# Schematic_IR__1_1.net
KiCad netlist of a schematic drawn in EAGLE
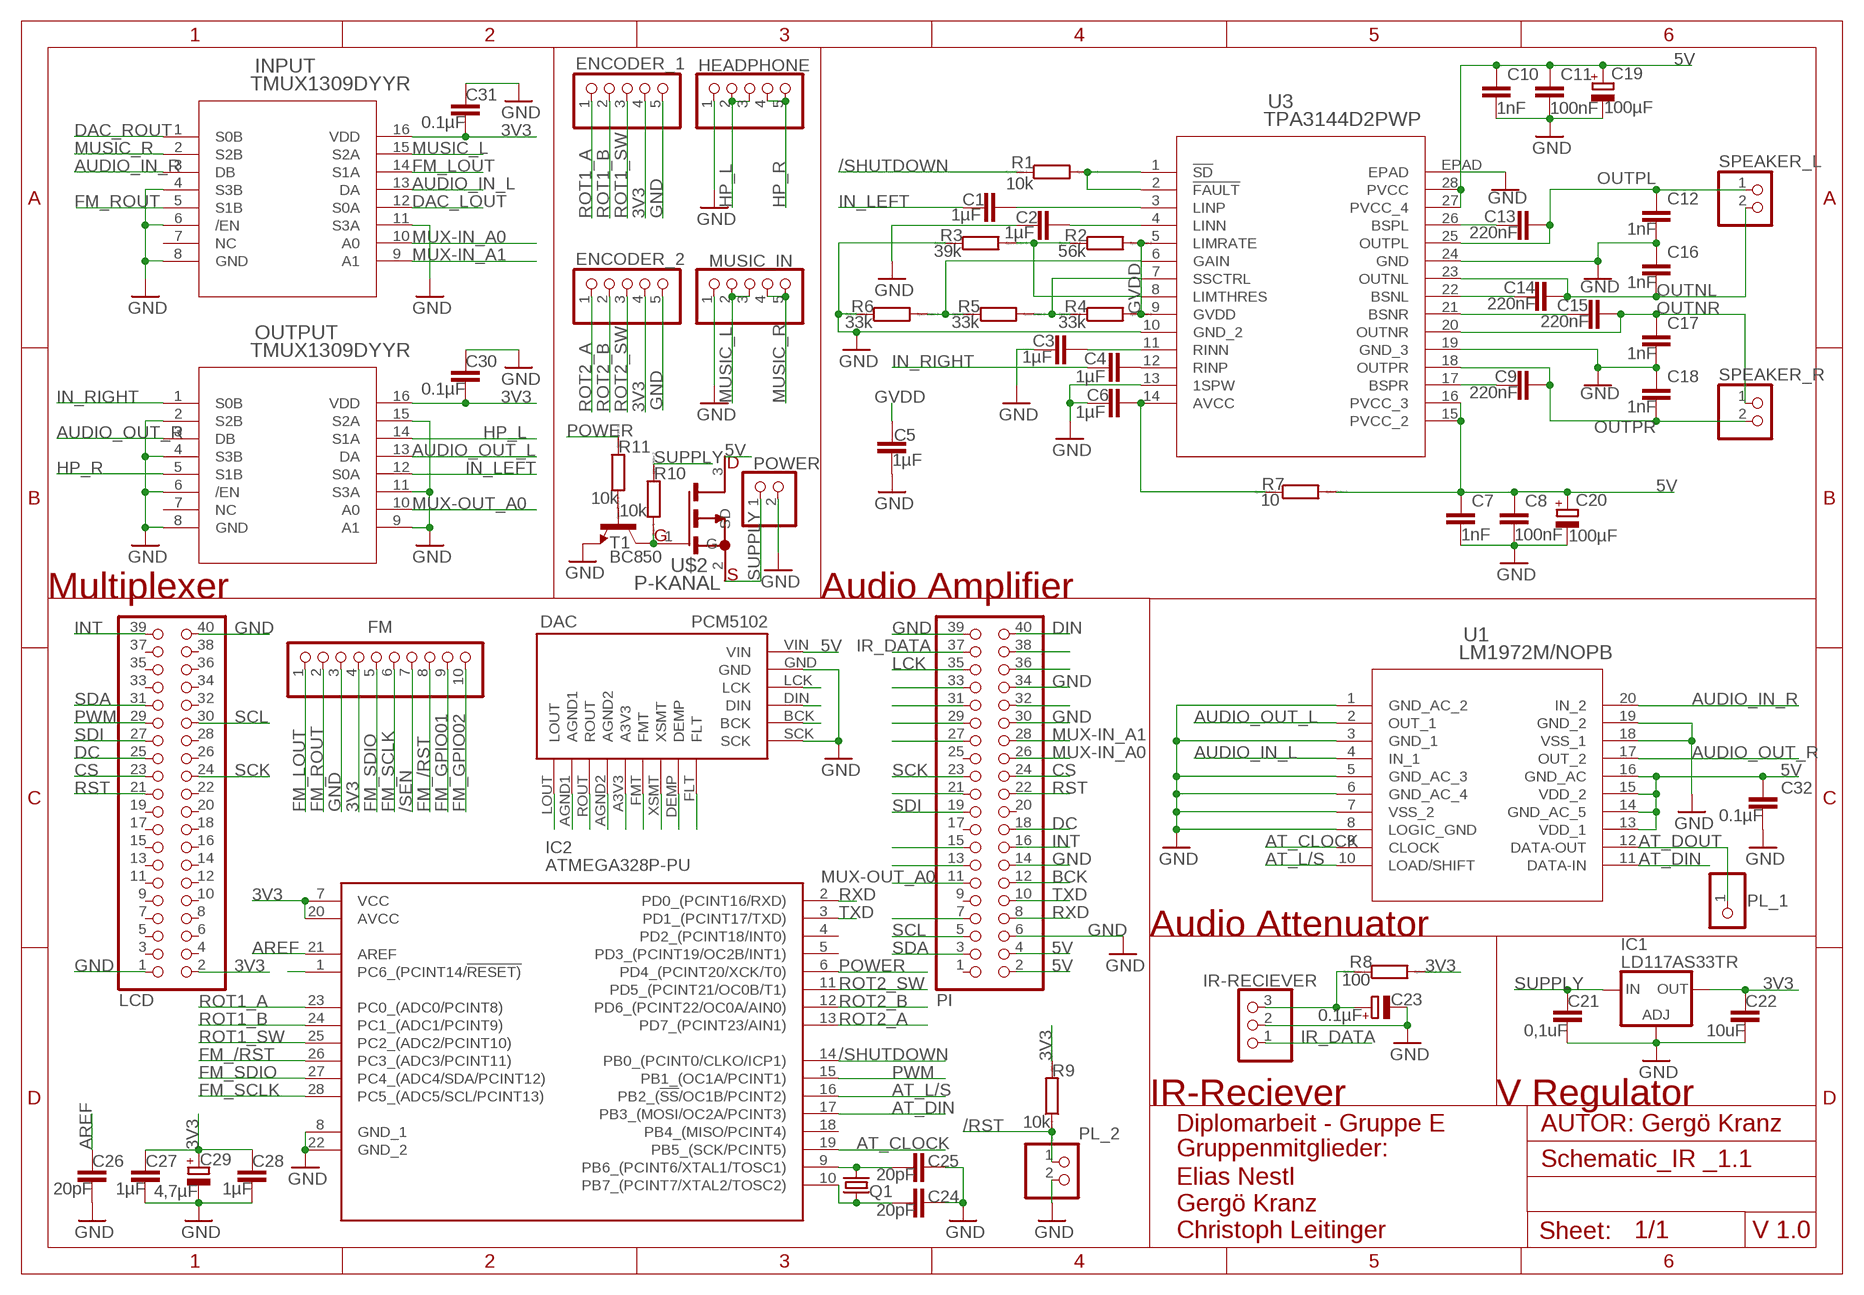
[diagram p0: schematic, sheet 1]

(export (version "E")
  (design (tool "Eeschema 10.0.6"))
  (components
    (comp (ref "C1")
      (value "1µF")
      (footprint "eagle-import:C0603K")
      (libsource (lib "eagle-import") (part "C-EUC0603K"))
    )
    (comp (ref "C2")
      (value "1µF")
      (footprint "eagle-import:C0603K")
      (libsource (lib "eagle-import") (part "C-EUC0603K"))
    )
    (comp (ref "C3")
      (value "1µF")
      (footprint "eagle-import:C0603K")
      (libsource (lib "eagle-import") (part "C-EUC0603K"))
    )
    (comp (ref "C4")
      (value "1µF")
      (footprint "eagle-import:C0603K")
      (libsource (lib "eagle-import") (part "C-EUC0603K"))
    )
    (comp (ref "C5")
      (value "1µF")
      (footprint "eagle-import:C0603K")
      (libsource (lib "eagle-import") (part "C-EUC0603K"))
    )
    (comp (ref "C6")
      (value "1µF")
      (footprint "eagle-import:C0603K")
      (libsource (lib "eagle-import") (part "C-EUC0603K"))
    )
    (comp (ref "C7")
      (value "1nF")
      (footprint "eagle-import:C0603K")
      (libsource (lib "eagle-import") (part "C-EUC0603K"))
    )
    (comp (ref "C8")
      (value "100nF")
      (footprint "eagle-import:C0603K")
      (libsource (lib "eagle-import") (part "C-EUC0603K"))
    )
    (comp (ref "C9")
      (value "220nF")
      (footprint "eagle-import:C0603K")
      (libsource (lib "eagle-import") (part "C-EUC0603K"))
    )
    (comp (ref "C10")
      (value "1nF")
      (footprint "eagle-import:C0603K")
      (libsource (lib "eagle-import") (part "C-EUC0603K"))
    )
    (comp (ref "C11")
      (value "100nF")
      (footprint "eagle-import:C0603K")
      (libsource (lib "eagle-import") (part "C-EUC0603K"))
    )
    (comp (ref "C12")
      (value "1nF")
      (footprint "eagle-import:C0603K")
      (libsource (lib "eagle-import") (part "C-EUC0603K"))
    )
    (comp (ref "C13")
      (value "220nF")
      (footprint "eagle-import:C0603K")
      (libsource (lib "eagle-import") (part "C-EUC0603K"))
    )
    (comp (ref "C14")
      (value "220nF")
      (footprint "eagle-import:C0603K")
      (libsource (lib "eagle-import") (part "C-EUC0603K"))
    )
    (comp (ref "C15")
      (value "220nF")
      (footprint "eagle-import:C0603K")
      (libsource (lib "eagle-import") (part "C-EUC0603K"))
    )
    (comp (ref "C16")
      (value "1nF")
      (footprint "eagle-import:C0603K")
      (libsource (lib "eagle-import") (part "C-EUC0603K"))
    )
    (comp (ref "C17")
      (value "1nF")
      (footprint "eagle-import:C0603K")
      (libsource (lib "eagle-import") (part "C-EUC0603K"))
    )
    (comp (ref "C18")
      (value "1nF")
      (footprint "eagle-import:C0603K")
      (libsource (lib "eagle-import") (part "C-EUC0603K"))
    )
    (comp (ref "C19")
      (value "100µF")
      (footprint "eagle-import:SMC_B")
      (libsource (lib "eagle-import") (part "CPOL-EUSMCB"))
    )
    (comp (ref "C20")
      (value "100µF")
      (footprint "eagle-import:SMC_B")
      (libsource (lib "eagle-import") (part "CPOL-EUSMCB"))
    )
    (comp (ref "C21")
      (value "0,1uF")
      (footprint "eagle-import:C0603K")
      (libsource (lib "eagle-import") (part "C-EUC0603K"))
    )
    (comp (ref "C22")
      (value "10uF")
      (footprint "eagle-import:C0603K")
      (libsource (lib "eagle-import") (part "C-EUC0603K"))
    )
    (comp (ref "C23")
      (value "0.1µF")
      (footprint "eagle-import:SMC_B")
      (libsource (lib "eagle-import") (part "CPOL-EUSMCB"))
    )
    (comp (ref "C24")
      (value "20pF")
      (footprint "eagle-import:C0603K")
      (libsource (lib "eagle-import") (part "C-EUC0603K"))
    )
    (comp (ref "C25")
      (value "20pF")
      (footprint "eagle-import:C0603K")
      (libsource (lib "eagle-import") (part "C-EUC0603K"))
    )
    (comp (ref "C26")
      (value "20pF")
      (footprint "eagle-import:C0603K")
      (libsource (lib "eagle-import") (part "C-EUC0603K"))
    )
    (comp (ref "C27")
      (value "1µF")
      (footprint "eagle-import:C0603K")
      (libsource (lib "eagle-import") (part "C-EUC0603K"))
    )
    (comp (ref "C28")
      (value "1µF")
      (footprint "eagle-import:C0603K")
      (libsource (lib "eagle-import") (part "C-EUC0603K"))
    )
    (comp (ref "C29")
      (value "4,7µF")
      (footprint "eagle-import:SMC_B")
      (libsource (lib "eagle-import") (part "CPOL-EUSMCB"))
    )
    (comp (ref "C30")
      (value "0.1µF")
      (footprint "eagle-import:C0603K")
      (libsource (lib "eagle-import") (part "C-EUC0603K"))
    )
    (comp (ref "C31")
      (value "0.1µF")
      (footprint "eagle-import:C0603K")
      (libsource (lib "eagle-import") (part "C-EUC0603K"))
    )
    (comp (ref "C32")
      (value "0.1µF")
      (footprint "eagle-import:C0603K")
      (libsource (lib "eagle-import") (part "C-EUC0603K"))
    )
    (comp (ref "DAC")
      (value "PCM5102")
      (footprint "eagle-import:PCM5102")
      (libsource (lib "eagle-import") (part "PCM5102"))
    )
    (comp (ref "ENCODER_1")
      (value "PINHD-1X5")
      (footprint "eagle-import:1X05")
      (libsource (lib "eagle-import") (part "PINHD-1X5"))
    )
    (comp (ref "ENCODER_2")
      (value "PINHD-1X5")
      (footprint "eagle-import:1X05")
      (libsource (lib "eagle-import") (part "PINHD-1X5"))
    )
    (comp (ref "FM")
      (value "PINHD-1X10_2.54")
      (footprint "eagle-import:1X10")
      (libsource (lib "eagle-import") (part "PINHD-1X10_2.54"))
    )
    (comp (ref "HEADPHONE")
      (value "PINHD-1X5_2.54")
      (footprint "eagle-import:1X05")
      (libsource (lib "eagle-import") (part "PINHD-1X5_2.54"))
    )
    (comp (ref "IC1")
      (value "LD117AS33TR")
      (footprint "eagle-import:SOT223")
      (libsource (lib "eagle-import") (part "LD117A?S33TR"))
    )
    (comp (ref "IC2")
      (value "ATMEGA328P-PU")
      (footprint "eagle-import:DIP794W53P254L3467H457Q28N")
      (fields (field (name "MOUSER_PART_NUMBER") "556-ATMEGA328P-PU"))
      (libsource (lib "eagle-import") (part "ATMEGA328P-PU"))
    )
    (comp (ref "INPUT")
      (value "TMUX1309DYYR")
      (footprint "eagle-import:SOIC_309DYYR_TEX")
      (fields (field (name "COPYRIGHT") "Copyright (C) 2018 Accelerated Designs. All rights reserved"))
      (libsource (lib "eagle-import") (part "TMUX1309DYYR"))
    )
    (comp (ref "IR-RECIEVER")
      (value "PINHD-1X3_2.54")
      (footprint "eagle-import:1X03")
      (libsource (lib "eagle-import") (part "PINHD-1X3_2.54"))
    )
    (comp (ref "LCD")
      (value "PINHD-2X20")
      (footprint "eagle-import:2X20")
      (libsource (lib "eagle-import") (part "PINHD-2X20"))
    )
    (comp (ref "MUSIC_IN")
      (value "PINHD-1X5_2.54")
      (footprint "eagle-import:1X05")
      (libsource (lib "eagle-import") (part "PINHD-1X5_2.54"))
    )
    (comp (ref "OUTPUT")
      (value "TMUX1309DYYR")
      (footprint "eagle-import:SOIC_309DYYR_TEX")
      (fields (field (name "COPYRIGHT") "Copyright (C) 2018 Accelerated Designs. All rights reserved"))
      (libsource (lib "eagle-import") (part "TMUX1309DYYR"))
    )
    (comp (ref "PI")
      (value "PINHD-2X20")
      (footprint "eagle-import:2X20")
      (libsource (lib "eagle-import") (part "PINHD-2X20"))
    )
    (comp (ref "PL_1")
      (value "PINHD-1X1_2.00")
      (footprint "eagle-import:1X01M")
      (libsource (lib "eagle-import") (part "PINHD-1X1_2.00"))
    )
    (comp (ref "PL_2")
      (value "PINHD-1X2_2.00")
      (footprint "eagle-import:1X02M")
      (libsource (lib "eagle-import") (part "PINHD-1X2_2.00"))
    )
    (comp (ref "POWER")
      (value "PINHD-1X2_2.54")
      (footprint "eagle-import:1X02")
      (libsource (lib "eagle-import") (part "PINHD-1X2_2.54"))
    )
    (comp (ref "Q1")
      (value "KX-KS")
      (footprint "eagle-import:11.4X4.5")
      (libsource (lib "eagle-import") (part "KX-KS"))
    )
    (comp (ref "R1")
      (value "10k")
      (footprint "eagle-import:R0603")
      (libsource (lib "eagle-import") (part "RR0603"))
    )
    (comp (ref "R2")
      (value "56k")
      (footprint "eagle-import:R0603")
      (libsource (lib "eagle-import") (part "RR0603"))
    )
    (comp (ref "R3")
      (value "39k")
      (footprint "eagle-import:R0603")
      (libsource (lib "eagle-import") (part "RR0603"))
    )
    (comp (ref "R4")
      (value "33k")
      (footprint "eagle-import:R0603")
      (libsource (lib "eagle-import") (part "RR0603"))
    )
    (comp (ref "R5")
      (value "33k")
      (footprint "eagle-import:R0603")
      (libsource (lib "eagle-import") (part "RR0603"))
    )
    (comp (ref "R6")
      (value "33k")
      (footprint "eagle-import:R0603")
      (libsource (lib "eagle-import") (part "RR0603"))
    )
    (comp (ref "R7")
      (value "10")
      (footprint "eagle-import:R0603")
      (libsource (lib "eagle-import") (part "RR0603"))
    )
    (comp (ref "R8")
      (value "100")
      (footprint "eagle-import:R0603")
      (libsource (lib "eagle-import") (part "RR0603"))
    )
    (comp (ref "R9")
      (value "10k")
      (footprint "eagle-import:R0603")
      (libsource (lib "eagle-import") (part "RR0603"))
    )
    (comp (ref "R10")
      (value "10k")
      (footprint "eagle-import:R0603")
      (libsource (lib "eagle-import") (part "RR0603"))
    )
    (comp (ref "R11")
      (value "10k")
      (footprint "eagle-import:R0603")
      (libsource (lib "eagle-import") (part "RR0603"))
    )
    (comp (ref "SPEAKER_L")
      (value "PINHD-1X2_2.54")
      (footprint "eagle-import:1X02")
      (libsource (lib "eagle-import") (part "PINHD-1X2_2.54"))
    )
    (comp (ref "SPEAKER_R")
      (value "PINHD-1X2_2.54")
      (footprint "eagle-import:1X02")
      (libsource (lib "eagle-import") (part "PINHD-1X2_2.54"))
    )
    (comp (ref "T1")
      (value "BC850")
      (footprint "eagle-import:SOT23")
      (libsource (lib "eagle-import") (part "BC850"))
    )
    (comp (ref "U$2")
      (value "P-KANAL")
      (footprint "eagle-import:SOT23")
      (libsource (lib "eagle-import") (part "P-KANAL"))
    )
    (comp (ref "U1")
      (value "LM1972M/NOPB")
      (footprint "eagle-import:M20B_TEX")
      (libsource (lib "eagle-import") (part "LM1972M/NOPB"))
    )
    (comp (ref "U3")
      (value "TPA3144D2PWP")
      (footprint "eagle-import:PWP28_2P4X3.4_TEX")
      (fields (field (name "COPYRIGHT") "Copyright (C) 2018 Accelerated Designs. All rights reserved"))
      (libsource (lib "eagle-import") (part "TPA3144D2PWP"))
    )
  )
  (nets
    (net (code "1") (name "/3V3") (class "Default")
      (node (ref "C22") (pin "2") (pinfunction "2_2") (pintype "passive"))
      (node (ref "C27") (pin "1") (pinfunction "1_1") (pintype "passive"))
      (node (ref "C28") (pin "1") (pinfunction "1_1") (pintype "passive"))
      (node (ref "C29") (pin "+") (pinfunction "+_+") (pintype "passive"))
      (node (ref "C30") (pin "2") (pinfunction "2_2") (pintype "passive"))
      (node (ref "C31") (pin "2") (pinfunction "2_2") (pintype "passive"))
      (node (ref "ENCODER_1") (pin "4") (pinfunction "4_4") (pintype "passive"))
      (node (ref "ENCODER_2") (pin "4") (pinfunction "4_4") (pintype "passive"))
      (node (ref "FM") (pin "4") (pinfunction "4_4") (pintype "passive"))
      (node (ref "IC1") (pin "4") (pinfunction "OUT_4") (pintype "passive"))
      (node (ref "IC2") (pin "20") (pinfunction "AVCC_20") (pintype "bidirectional"))
      (node (ref "IC2") (pin "7") (pinfunction "VCC_7") (pintype "bidirectional"))
      (node (ref "INPUT") (pin "16") (pinfunction "VDD_16") (pintype "power_in"))
      (node (ref "LCD") (pin "2") (pinfunction "2_2") (pintype "passive"))
      (node (ref "OUTPUT") (pin "16") (pinfunction "VDD_16") (pintype "power_in"))
      (node (ref "R8") (pin "2") (pinfunction "2_2") (pintype "passive"))
      (node (ref "R9") (pin "2") (pinfunction "2_2") (pintype "passive"))
    )
    (net (code "2") (name "/5V") (class "Default")
      (node (ref "C10") (pin "1") (pinfunction "1_1") (pintype "passive"))
      (node (ref "C11") (pin "1") (pinfunction "1_1") (pintype "passive"))
      (node (ref "C19") (pin "+") (pinfunction "+_+") (pintype "passive"))
      (node (ref "C20") (pin "+") (pinfunction "+_+") (pintype "passive"))
      (node (ref "C32") (pin "1") (pinfunction "1_1") (pintype "passive"))
      (node (ref "C7") (pin "1") (pinfunction "1_1") (pintype "passive"))
      (node (ref "C8") (pin "1") (pinfunction "1_1") (pintype "passive"))
      (node (ref "DAC") (pin "VIN") (pinfunction "VIN_VIN") (pintype "bidirectional"))
      (node (ref "PI") (pin "2") (pinfunction "2_2") (pintype "passive"))
      (node (ref "PI") (pin "4") (pinfunction "4_4") (pintype "passive"))
      (node (ref "R7") (pin "2") (pinfunction "2_2") (pintype "passive"))
      (node (ref "U$2") (pin "3") (pinfunction "D_3") (pintype "bidirectional"))
      (node (ref "U1") (pin "13") (pinfunction "VDD_1_13") (pintype "power_in"))
      (node (ref "U1") (pin "14") (pinfunction "GND_AC_5_14") (pintype "power_in"))
      (node (ref "U1") (pin "15") (pinfunction "VDD_2_15") (pintype "power_in"))
      (node (ref "U1") (pin "16") (pinfunction "GND_AC_16") (pintype "power_in"))
      (node (ref "U3") (pin "15") (pinfunction "PVCC_2_15") (pintype "passive"))
      (node (ref "U3") (pin "16") (pinfunction "PVCC_3_16") (pintype "passive"))
      (node (ref "U3") (pin "27") (pinfunction "PVCC_4_27") (pintype "passive"))
      (node (ref "U3") (pin "28") (pinfunction "PVCC_28") (pintype "passive"))
    )
    (net (code "3") (name "/AREF") (class "Default")
      (node (ref "C26") (pin "1") (pinfunction "1_1") (pintype "passive"))
      (node (ref "IC2") (pin "21") (pinfunction "AREF_21") (pintype "bidirectional"))
    )
    (net (code "4") (name "/AT_CLOCK") (class "Default")
      (node (ref "IC2") (pin "19") (pinfunction "PB5_(SCK/PCINT5)_19") (pintype "bidirectional"))
      (node (ref "U1") (pin "9") (pinfunction "CLOCK_9") (pintype "input"))
    )
    (net (code "5") (name "/AT_DIN") (class "Default")
      (node (ref "IC2") (pin "17") (pinfunction "PB3_(MOSI/OC2A/PCINT3)_17") (pintype "bidirectional"))
      (node (ref "U1") (pin "11") (pinfunction "DATA-IN_11") (pintype "input"))
    )
    (net (code "6") (name "/AT_DOUT") (class "Default")
      (node (ref "PL_1") (pin "1") (pinfunction "1_1") (pintype "passive"))
      (node (ref "U1") (pin "12") (pinfunction "DATA-OUT_12") (pintype "output"))
    )
    (net (code "7") (name "/AT_L{slash}S") (class "Default")
      (node (ref "IC2") (pin "16") (pinfunction "PB2_(~{SS}/OC1B/PCINT2)_16") (pintype "bidirectional"))
      (node (ref "U1") (pin "10") (pinfunction "LOAD/SHIFT_10") (pintype "input"))
    )
    (net (code "8") (name "/AUDIO_IN_L") (class "Default")
      (node (ref "INPUT") (pin "13") (pinfunction "DA_13") (pintype "passive"))
      (node (ref "U1") (pin "4") (pinfunction "IN_1_4") (pintype "input"))
    )
    (net (code "9") (name "/AUDIO_IN_R") (class "Default")
      (node (ref "INPUT") (pin "3") (pinfunction "DB_3") (pintype "passive"))
      (node (ref "U1") (pin "20") (pinfunction "IN_2_20") (pintype "input"))
    )
    (net (code "10") (name "/AUDIO_OUT_L") (class "Default")
      (node (ref "OUTPUT") (pin "13") (pinfunction "DA_13") (pintype "passive"))
      (node (ref "U1") (pin "2") (pinfunction "OUT_1_2") (pintype "output"))
    )
    (net (code "11") (name "/AUDIO_OUT_R") (class "Default")
      (node (ref "OUTPUT") (pin "3") (pinfunction "DB_3") (pintype "passive"))
      (node (ref "U1") (pin "17") (pinfunction "OUT_2_17") (pintype "output"))
    )
    (net (code "12") (name "/BCK") (class "Default")
      (node (ref "DAC") (pin "BCK") (pinfunction "BCK_BCK") (pintype "bidirectional"))
      (node (ref "PI") (pin "12") (pinfunction "12_12") (pintype "passive"))
    )
    (net (code "13") (name "/CS") (class "Default")
      (node (ref "LCD") (pin "23") (pinfunction "23_23") (pintype "passive"))
      (node (ref "PI") (pin "24") (pinfunction "24_24") (pintype "passive"))
    )
    (net (code "14") (name "/DAC_LOUT") (class "Default")
      (node (ref "DAC") (pin "LOUT") (pinfunction "LOUT_LOUT") (pintype "bidirectional"))
      (node (ref "INPUT") (pin "12") (pinfunction "S0A_12") (pintype "bidirectional"))
    )
    (net (code "15") (name "/DAC_ROUT") (class "Default")
      (node (ref "DAC") (pin "ROUT") (pinfunction "ROUT_ROUT") (pintype "bidirectional"))
      (node (ref "INPUT") (pin "1") (pinfunction "S0B_1") (pintype "bidirectional"))
    )
    (net (code "16") (name "/DC") (class "Default")
      (node (ref "LCD") (pin "25") (pinfunction "25_25") (pintype "passive"))
      (node (ref "PI") (pin "18") (pinfunction "18_18") (pintype "passive"))
    )
    (net (code "17") (name "/DIN") (class "Default")
      (node (ref "DAC") (pin "DIN") (pinfunction "DIN_DIN") (pintype "bidirectional"))
      (node (ref "PI") (pin "40") (pinfunction "40_40") (pintype "passive"))
    )
    (net (code "18") (name "/FM_GPIO01") (class "Default")
      (node (ref "FM") (pin "9") (pinfunction "9_9") (pintype "passive"))
    )
    (net (code "19") (name "/FM_GPIO02") (class "Default")
      (node (ref "FM") (pin "10") (pinfunction "10_10") (pintype "passive"))
    )
    (net (code "20") (name "/FM_LOUT") (class "Default")
      (node (ref "FM") (pin "1") (pinfunction "1_1") (pintype "passive"))
      (node (ref "INPUT") (pin "14") (pinfunction "S1A_14") (pintype "bidirectional"))
    )
    (net (code "21") (name "/FM_ROUT") (class "Default")
      (node (ref "FM") (pin "2") (pinfunction "2_2") (pintype "passive"))
      (node (ref "INPUT") (pin "5") (pinfunction "S1B_5") (pintype "bidirectional"))
    )
    (net (code "22") (name "/FM_SCLK") (class "Default")
      (node (ref "FM") (pin "6") (pinfunction "6_6") (pintype "passive"))
      (node (ref "IC2") (pin "28") (pinfunction "PC5_(ADC5/SCL/PCINT13)_28") (pintype "bidirectional"))
    )
    (net (code "23") (name "/FM_SDIO") (class "Default")
      (node (ref "FM") (pin "5") (pinfunction "5_5") (pintype "passive"))
      (node (ref "IC2") (pin "27") (pinfunction "PC4_(ADC4/SDA/PCINT12)_27") (pintype "bidirectional"))
    )
    (net (code "24") (name "/FM_{slash}RST") (class "Default")
      (node (ref "FM") (pin "8") (pinfunction "8_8") (pintype "passive"))
      (node (ref "IC2") (pin "26") (pinfunction "PC3_(ADC3/PCINT11)_26") (pintype "bidirectional"))
    )
    (net (code "25") (name "/GVDD") (class "Default")
      (node (ref "C5") (pin "1") (pinfunction "1_1") (pintype "passive"))
      (node (ref "R2") (pin "2") (pinfunction "2_2") (pintype "passive"))
      (node (ref "R4") (pin "2") (pinfunction "2_2") (pintype "passive"))
      (node (ref "U3") (pin "5") (pinfunction "LIMRATE_5") (pintype "passive"))
      (node (ref "U3") (pin "9") (pinfunction "GVDD_9") (pintype "power_in"))
    )
    (net (code "26") (name "/HP_L") (class "Default")
      (node (ref "HEADPHONE") (pin "2") (pinfunction "2_2") (pintype "passive"))
      (node (ref "HEADPHONE") (pin "3") (pinfunction "3_3") (pintype "passive"))
      (node (ref "OUTPUT") (pin "14") (pinfunction "S1A_14") (pintype "bidirectional"))
    )
    (net (code "27") (name "/HP_R") (class "Default")
      (node (ref "HEADPHONE") (pin "4") (pinfunction "4_4") (pintype "passive"))
      (node (ref "HEADPHONE") (pin "5") (pinfunction "5_5") (pintype "passive"))
      (node (ref "OUTPUT") (pin "5") (pinfunction "S1B_5") (pintype "bidirectional"))
    )
    (net (code "28") (name "/INT") (class "Default")
      (node (ref "LCD") (pin "39") (pinfunction "39_39") (pintype "passive"))
      (node (ref "PI") (pin "16") (pinfunction "16_16") (pintype "passive"))
    )
    (net (code "29") (name "/IN_LEFT") (class "Default")
      (node (ref "C1") (pin "1") (pinfunction "1_1") (pintype "passive"))
      (node (ref "OUTPUT") (pin "12") (pinfunction "S0A_12") (pintype "bidirectional"))
    )
    (net (code "30") (name "/IN_RIGHT") (class "Default")
      (node (ref "C4") (pin "1") (pinfunction "1_1") (pintype "passive"))
      (node (ref "OUTPUT") (pin "1") (pinfunction "S0B_1") (pintype "bidirectional"))
    )
    (net (code "31") (name "/IR_DATA") (class "Default")
      (node (ref "IR-RECIEVER") (pin "1") (pinfunction "1_1") (pintype "passive"))
      (node (ref "PI") (pin "37") (pinfunction "37_37") (pintype "passive"))
    )
    (net (code "32") (name "/LCK") (class "Default")
      (node (ref "DAC") (pin "LCK") (pinfunction "LCK_LCK") (pintype "bidirectional"))
      (node (ref "PI") (pin "35") (pinfunction "35_35") (pintype "passive"))
    )
    (net (code "33") (name "/MUSIC_L") (class "Default")
      (node (ref "INPUT") (pin "15") (pinfunction "S2A_15") (pintype "bidirectional"))
      (node (ref "MUSIC_IN") (pin "2") (pinfunction "2_2") (pintype "passive"))
      (node (ref "MUSIC_IN") (pin "3") (pinfunction "3_3") (pintype "passive"))
    )
    (net (code "34") (name "/MUSIC_R") (class "Default")
      (node (ref "INPUT") (pin "2") (pinfunction "S2B_2") (pintype "bidirectional"))
      (node (ref "MUSIC_IN") (pin "4") (pinfunction "4_4") (pintype "passive"))
      (node (ref "MUSIC_IN") (pin "5") (pinfunction "5_5") (pintype "passive"))
    )
    (net (code "35") (name "/MUX-IN_A0") (class "Default")
      (node (ref "INPUT") (pin "10") (pinfunction "A0_10") (pintype "bidirectional"))
      (node (ref "PI") (pin "26") (pinfunction "26_26") (pintype "passive"))
    )
    (net (code "36") (name "/MUX-IN_A1") (class "Default")
      (node (ref "INPUT") (pin "9") (pinfunction "A1_9") (pintype "bidirectional"))
      (node (ref "PI") (pin "28") (pinfunction "28_28") (pintype "passive"))
    )
    (net (code "37") (name "/MUX-OUT_A0") (class "Default")
      (node (ref "OUTPUT") (pin "10") (pinfunction "A0_10") (pintype "bidirectional"))
      (node (ref "PI") (pin "11") (pinfunction "11_11") (pintype "passive"))
    )
    (net (code "38") (name "/OUTNL") (class "Default")
      (node (ref "C14") (pin "2") (pinfunction "2_2") (pintype "passive"))
      (node (ref "C16") (pin "2") (pinfunction "2_2") (pintype "passive"))
      (node (ref "SPEAKER_L") (pin "2") (pinfunction "2_2") (pintype "passive"))
      (node (ref "U3") (pin "23") (pinfunction "OUTNL_23") (pintype "output"))
    )
    (net (code "39") (name "/OUTNR") (class "Default")
      (node (ref "C15") (pin "2") (pinfunction "2_2") (pintype "passive"))
      (node (ref "C17") (pin "1") (pinfunction "1_1") (pintype "passive"))
      (node (ref "SPEAKER_R") (pin "1") (pinfunction "1_1") (pintype "passive"))
      (node (ref "U3") (pin "20") (pinfunction "OUTNR_20") (pintype "output"))
    )
    (net (code "40") (name "/OUTPL") (class "Default")
      (node (ref "C12") (pin "1") (pinfunction "1_1") (pintype "passive"))
      (node (ref "C13") (pin "2") (pinfunction "2_2") (pintype "passive"))
      (node (ref "SPEAKER_L") (pin "1") (pinfunction "1_1") (pintype "passive"))
      (node (ref "U3") (pin "25") (pinfunction "OUTPL_25") (pintype "output"))
    )
    (net (code "41") (name "/OUTPR") (class "Default")
      (node (ref "C18") (pin "2") (pinfunction "2_2") (pintype "passive"))
      (node (ref "C9") (pin "2") (pinfunction "2_2") (pintype "passive"))
      (node (ref "SPEAKER_R") (pin "2") (pinfunction "2_2") (pintype "passive"))
      (node (ref "U3") (pin "18") (pinfunction "OUTPR_18") (pintype "output"))
    )
    (net (code "42") (name "/POWER") (class "Default")
      (node (ref "IC2") (pin "6") (pinfunction "PD4_(PCINT20/XCK/T0)_6") (pintype "bidirectional"))
      (node (ref "R11") (pin "1") (pinfunction "1_1") (pintype "passive"))
    )
    (net (code "43") (name "/PWM") (class "Default")
      (node (ref "IC2") (pin "15") (pinfunction "PB1_(OC1A/PCINT1)_15") (pintype "bidirectional"))
      (node (ref "LCD") (pin "29") (pinfunction "29_29") (pintype "passive"))
    )
    (net (code "44") (name "/ROT1_A") (class "Default")
      (node (ref "ENCODER_1") (pin "1") (pinfunction "1_1") (pintype "passive"))
      (node (ref "IC2") (pin "23") (pinfunction "PC0_(ADC0/PCINT8)_23") (pintype "bidirectional"))
    )
    (net (code "45") (name "/ROT1_B") (class "Default")
      (node (ref "ENCODER_1") (pin "2") (pinfunction "2_2") (pintype "passive"))
      (node (ref "IC2") (pin "24") (pinfunction "PC1_(ADC1/PCINT9)_24") (pintype "bidirectional"))
    )
    (net (code "46") (name "/ROT1_SW") (class "Default")
      (node (ref "ENCODER_1") (pin "3") (pinfunction "3_3") (pintype "passive"))
      (node (ref "IC2") (pin "25") (pinfunction "PC2_(ADC2/PCINT10)_25") (pintype "bidirectional"))
    )
    (net (code "47") (name "/ROT2_A") (class "Default")
      (node (ref "ENCODER_2") (pin "1") (pinfunction "1_1") (pintype "passive"))
      (node (ref "IC2") (pin "13") (pinfunction "PD7_(PCINT23/AIN1)_13") (pintype "bidirectional"))
    )
    (net (code "48") (name "/ROT2_B") (class "Default")
      (node (ref "ENCODER_2") (pin "2") (pinfunction "2_2") (pintype "passive"))
      (node (ref "IC2") (pin "12") (pinfunction "PD6_(PCINT22/OC0A/AIN0)_12") (pintype "bidirectional"))
    )
    (net (code "49") (name "/ROT2_SW") (class "Default")
      (node (ref "ENCODER_2") (pin "3") (pinfunction "3_3") (pintype "passive"))
      (node (ref "IC2") (pin "11") (pinfunction "PD5_(PCINT21/OC0B/T1)_11") (pintype "bidirectional"))
    )
    (net (code "50") (name "/RST") (class "Default")
      (node (ref "LCD") (pin "21") (pinfunction "21_21") (pintype "passive"))
      (node (ref "PI") (pin "22") (pinfunction "22_22") (pintype "passive"))
    )
    (net (code "51") (name "/RXD") (class "Default")
      (node (ref "IC2") (pin "2") (pinfunction "PD0_(PCINT16/RXD)_2") (pintype "bidirectional"))
      (node (ref "PI") (pin "8") (pinfunction "8_8") (pintype "passive"))
    )
    (net (code "52") (name "/SCK") (class "Default")
      (node (ref "LCD") (pin "24") (pinfunction "24_24") (pintype "passive"))
      (node (ref "PI") (pin "23") (pinfunction "23_23") (pintype "passive"))
    )
    (net (code "53") (name "/SCL") (class "Default")
      (node (ref "LCD") (pin "30") (pinfunction "30_30") (pintype "passive"))
      (node (ref "PI") (pin "5") (pinfunction "5_5") (pintype "passive"))
    )
    (net (code "54") (name "/SDA") (class "Default")
      (node (ref "LCD") (pin "31") (pinfunction "31_31") (pintype "passive"))
      (node (ref "PI") (pin "3") (pinfunction "3_3") (pintype "passive"))
    )
    (net (code "55") (name "/SDI") (class "Default")
      (node (ref "LCD") (pin "27") (pinfunction "27_27") (pintype "passive"))
      (node (ref "PI") (pin "19") (pinfunction "19_19") (pintype "passive"))
    )
    (net (code "56") (name "/SUPPLY") (class "Default")
      (node (ref "C21") (pin "2") (pinfunction "2_2") (pintype "passive"))
      (node (ref "IC1") (pin "3") (pinfunction "IN_3") (pintype "input"))
      (node (ref "POWER") (pin "1") (pinfunction "1_1") (pintype "passive"))
      (node (ref "R10") (pin "2") (pinfunction "2_2") (pintype "passive"))
      (node (ref "U$2") (pin "2") (pinfunction "S_2") (pintype "bidirectional"))
    )
    (net (code "57") (name "/TXD") (class "Default")
      (node (ref "IC2") (pin "3") (pinfunction "PD1_(PCINT17/TXD)_3") (pintype "bidirectional"))
      (node (ref "PI") (pin "10") (pinfunction "10_10") (pintype "passive"))
    )
    (net (code "58") (name "/{slash}RST") (class "Default")
      (node (ref "IC2") (pin "1") (pinfunction "PC6_(PCINT14/~{RESET})_1") (pintype "bidirectional"))
      (node (ref "PL_2") (pin "1") (pinfunction "1_1") (pintype "passive"))
      (node (ref "R9") (pin "1") (pinfunction "1_1") (pintype "passive"))
    )
    (net (code "59") (name "/{slash}SEN") (class "Default")
      (node (ref "FM") (pin "7") (pinfunction "7_7") (pintype "passive"))
    )
    (net (code "60") (name "/{slash}SHUTDOWN") (class "Default")
      (node (ref "IC2") (pin "14") (pinfunction "PB0_(PCINT0/CLKO/ICP1)_14") (pintype "bidirectional"))
      (node (ref "R1") (pin "1") (pinfunction "1_1") (pintype "passive"))
    )
    (net (code "61") (name "GND") (class "Default")
      (node (ref "C10") (pin "2") (pinfunction "2_2") (pintype "passive"))
      (node (ref "C11") (pin "2") (pinfunction "2_2") (pintype "passive"))
      (node (ref "C12") (pin "2") (pinfunction "2_2") (pintype "passive"))
      (node (ref "C16") (pin "1") (pinfunction "1_1") (pintype "passive"))
      (node (ref "C17") (pin "2") (pinfunction "2_2") (pintype "passive"))
      (node (ref "C18") (pin "1") (pinfunction "1_1") (pintype "passive"))
      (node (ref "C19") (pin "-") (pinfunction "-_-") (pintype "passive"))
      (node (ref "C2") (pin "1") (pinfunction "1_1") (pintype "passive"))
      (node (ref "C20") (pin "-") (pinfunction "-_-") (pintype "passive"))
      (node (ref "C21") (pin "1") (pinfunction "1_1") (pintype "passive"))
      (node (ref "C22") (pin "1") (pinfunction "1_1") (pintype "passive"))
      (node (ref "C23") (pin "-") (pinfunction "-_-") (pintype "passive"))
      (node (ref "C24") (pin "1") (pinfunction "1_1") (pintype "passive"))
      (node (ref "C25") (pin "1") (pinfunction "1_1") (pintype "passive"))
      (node (ref "C26") (pin "2") (pinfunction "2_2") (pintype "passive"))
      (node (ref "C27") (pin "2") (pinfunction "2_2") (pintype "passive"))
      (node (ref "C28") (pin "2") (pinfunction "2_2") (pintype "passive"))
      (node (ref "C29") (pin "-") (pinfunction "-_-") (pintype "passive"))
      (node (ref "C3") (pin "1") (pinfunction "1_1") (pintype "passive"))
      (node (ref "C30") (pin "1") (pinfunction "1_1") (pintype "passive"))
      (node (ref "C31") (pin "1") (pinfunction "1_1") (pintype "passive"))
      (node (ref "C32") (pin "2") (pinfunction "2_2") (pintype "passive"))
      (node (ref "C5") (pin "2") (pinfunction "2_2") (pintype "passive"))
      (node (ref "C6") (pin "1") (pinfunction "1_1") (pintype "passive"))
      (node (ref "C7") (pin "2") (pinfunction "2_2") (pintype "passive"))
      (node (ref "C8") (pin "2") (pinfunction "2_2") (pintype "passive"))
      (node (ref "DAC") (pin "GND") (pinfunction "GND_GND") (pintype "bidirectional"))
      (node (ref "DAC") (pin "SCK") (pinfunction "SCK_SCK") (pintype "bidirectional"))
      (node (ref "ENCODER_1") (pin "5") (pinfunction "5_5") (pintype "passive"))
      (node (ref "ENCODER_2") (pin "5") (pinfunction "5_5") (pintype "passive"))
      (node (ref "FM") (pin "3") (pinfunction "3_3") (pintype "passive"))
      (node (ref "HEADPHONE") (pin "1") (pinfunction "1_1") (pintype "passive"))
      (node (ref "IC1") (pin "1") (pinfunction "ADJ_1") (pintype "input"))
      (node (ref "IC2") (pin "22") (pinfunction "GND_2_22") (pintype "bidirectional"))
      (node (ref "IC2") (pin "8") (pinfunction "GND_1_8") (pintype "bidirectional"))
      (node (ref "INPUT") (pin "11") (pinfunction "S3A_11") (pintype "bidirectional"))
      (node (ref "INPUT") (pin "4") (pinfunction "S3B_4") (pintype "bidirectional"))
      (node (ref "INPUT") (pin "6") (pinfunction "/EN_6") (pintype "passive"))
      (node (ref "INPUT") (pin "8") (pinfunction "GND_8") (pintype "passive"))
      (node (ref "IR-RECIEVER") (pin "2") (pinfunction "2_2") (pintype "passive"))
      (node (ref "LCD") (pin "1") (pinfunction "1_1") (pintype "passive"))
      (node (ref "LCD") (pin "40") (pinfunction "40_40") (pintype "passive"))
      (node (ref "MUSIC_IN") (pin "1") (pinfunction "1_1") (pintype "passive"))
      (node (ref "OUTPUT") (pin "11") (pinfunction "S3A_11") (pintype "bidirectional"))
      (node (ref "OUTPUT") (pin "15") (pinfunction "S2A_15") (pintype "bidirectional"))
      (node (ref "OUTPUT") (pin "2") (pinfunction "S2B_2") (pintype "bidirectional"))
      (node (ref "OUTPUT") (pin "4") (pinfunction "S3B_4") (pintype "bidirectional"))
      (node (ref "OUTPUT") (pin "6") (pinfunction "/EN_6") (pintype "passive"))
      (node (ref "OUTPUT") (pin "8") (pinfunction "GND_8") (pintype "passive"))
      (node (ref "OUTPUT") (pin "9") (pinfunction "A1_9") (pintype "bidirectional"))
      (node (ref "PI") (pin "14") (pinfunction "14_14") (pintype "passive"))
      (node (ref "PI") (pin "30") (pinfunction "30_30") (pintype "passive"))
      (node (ref "PI") (pin "34") (pinfunction "34_34") (pintype "passive"))
      (node (ref "PI") (pin "39") (pinfunction "39_39") (pintype "passive"))
      (node (ref "PI") (pin "6") (pinfunction "6_6") (pintype "passive"))
      (node (ref "PL_2") (pin "2") (pinfunction "2_2") (pintype "passive"))
      (node (ref "POWER") (pin "2") (pinfunction "2_2") (pintype "passive"))
      (node (ref "R3") (pin "1") (pinfunction "1_1") (pintype "passive"))
      (node (ref "R6") (pin "1") (pinfunction "1_1") (pintype "passive"))
      (node (ref "T1") (pin "2") (pinfunction "E_2") (pintype "passive"))
      (node (ref "U1") (pin "1") (pinfunction "GND_AC_2_1") (pintype "power_in"))
      (node (ref "U1") (pin "18") (pinfunction "VSS_1_18") (pintype "power_in"))
      (node (ref "U1") (pin "19") (pinfunction "GND_2_19") (pintype "power_in"))
      (node (ref "U1") (pin "3") (pinfunction "GND_1_3") (pintype "power_in"))
      (node (ref "U1") (pin "5") (pinfunction "GND_AC_3_5") (pintype "power_in"))
      (node (ref "U1") (pin "6") (pinfunction "GND_AC_4_6") (pintype "power_in"))
      (node (ref "U1") (pin "7") (pinfunction "VSS_2_7") (pintype "power_in"))
      (node (ref "U1") (pin "8") (pinfunction "LOGIC_GND_8") (pintype "power_in"))
      (node (ref "U3") (pin "10") (pinfunction "GND_2_10") (pintype "passive"))
      (node (ref "U3") (pin "13") (pinfunction "1SPW_13") (pintype "passive"))
      (node (ref "U3") (pin "19") (pinfunction "GND_3_19") (pintype "passive"))
      (node (ref "U3") (pin "24") (pinfunction "GND_24") (pintype "passive"))
      (node (ref "U3") (pin "EPAD") (pinfunction "EPAD_EPAD") (pintype "passive"))
    )
    (net (code "62") (name "Net-(C23-Pad+)") (class "Default")
      (node (ref "C23") (pin "+") (pinfunction "+_+") (pintype "passive"))
      (node (ref "IR-RECIEVER") (pin "3") (pinfunction "3_3") (pintype "passive"))
      (node (ref "R8") (pin "1") (pinfunction "1_1") (pintype "passive"))
    )
    (net (code "63") (name "Net-(IC2-PB6_(PCINT6{slash}XTAL1{slash}TOSC1))") (class "Default")
      (node (ref "C25") (pin "2") (pinfunction "2_2") (pintype "passive"))
      (node (ref "IC2") (pin "9") (pinfunction "PB6_(PCINT6/XTAL1/TOSC1)_9") (pintype "bidirectional"))
      (node (ref "Q1") (pin "2") (pinfunction "2_2") (pintype "passive"))
    )
    (net (code "64") (name "Net-(IC2-PB7_(PCINT7{slash}XTAL2{slash}TOSC2))") (class "Default")
      (node (ref "C24") (pin "2") (pinfunction "2_2") (pintype "passive"))
      (node (ref "IC2") (pin "10") (pinfunction "PB7_(PCINT7/XTAL2/TOSC2)_10") (pintype "bidirectional"))
      (node (ref "Q1") (pin "1") (pinfunction "1_1") (pintype "passive"))
    )
    (net (code "65") (name "Net-(T1-B)") (class "Default")
      (node (ref "R11") (pin "2") (pinfunction "2_2") (pintype "passive"))
      (node (ref "T1") (pin "1") (pinfunction "B_1") (pintype "passive"))
    )
    (net (code "66") (name "Net-(T1-C)") (class "Default")
      (node (ref "R10") (pin "1") (pinfunction "1_1") (pintype "passive"))
      (node (ref "T1") (pin "3") (pinfunction "C_3") (pintype "passive"))
      (node (ref "U$2") (pin "1") (pinfunction "G_1") (pintype "bidirectional"))
    )
    (net (code "67") (name "Net-(U3-AVCC)") (class "Default")
      (node (ref "C6") (pin "2") (pinfunction "2_2") (pintype "passive"))
      (node (ref "R7") (pin "1") (pinfunction "1_1") (pintype "passive"))
      (node (ref "U3") (pin "14") (pinfunction "AVCC_14") (pintype "passive"))
    )
    (net (code "68") (name "Net-(U3-BSNL)") (class "Default")
      (node (ref "C14") (pin "1") (pinfunction "1_1") (pintype "passive"))
      (node (ref "U3") (pin "22") (pinfunction "BSNL_22") (pintype "passive"))
    )
    (net (code "69") (name "Net-(U3-BSNR)") (class "Default")
      (node (ref "C15") (pin "1") (pinfunction "1_1") (pintype "passive"))
      (node (ref "U3") (pin "21") (pinfunction "BSNR_21") (pintype "passive"))
    )
    (net (code "70") (name "Net-(U3-BSPL)") (class "Default")
      (node (ref "C13") (pin "1") (pinfunction "1_1") (pintype "passive"))
      (node (ref "U3") (pin "26") (pinfunction "BSPL_26") (pintype "passive"))
    )
    (net (code "71") (name "Net-(U3-BSPR)") (class "Default")
      (node (ref "C9") (pin "1") (pinfunction "1_1") (pintype "passive"))
      (node (ref "U3") (pin "17") (pinfunction "BSPR_17") (pintype "passive"))
    )
    (net (code "72") (name "Net-(U3-GAIN)") (class "Default")
      (node (ref "R5") (pin "1") (pinfunction "1_1") (pintype "passive"))
      (node (ref "R6") (pin "2") (pinfunction "2_2") (pintype "passive"))
      (node (ref "U3") (pin "6") (pinfunction "GAIN_6") (pintype "passive"))
    )
    (net (code "73") (name "Net-(U3-LIMTHRES)") (class "Default")
      (node (ref "R2") (pin "1") (pinfunction "1_1") (pintype "passive"))
      (node (ref "R3") (pin "2") (pinfunction "2_2") (pintype "passive"))
      (node (ref "U3") (pin "8") (pinfunction "LIMTHRES_8") (pintype "passive"))
    )
    (net (code "74") (name "Net-(U3-LINN)") (class "Default")
      (node (ref "C2") (pin "2") (pinfunction "2_2") (pintype "passive"))
      (node (ref "U3") (pin "4") (pinfunction "LINN_4") (pintype "passive"))
    )
    (net (code "75") (name "Net-(U3-LINP)") (class "Default")
      (node (ref "C1") (pin "2") (pinfunction "2_2") (pintype "passive"))
      (node (ref "U3") (pin "3") (pinfunction "LINP_3") (pintype "passive"))
    )
    (net (code "76") (name "Net-(U3-RINN)") (class "Default")
      (node (ref "C3") (pin "2") (pinfunction "2_2") (pintype "passive"))
      (node (ref "U3") (pin "11") (pinfunction "RINN_11") (pintype "passive"))
    )
    (net (code "77") (name "Net-(U3-RINP)") (class "Default")
      (node (ref "C4") (pin "2") (pinfunction "2_2") (pintype "passive"))
      (node (ref "U3") (pin "12") (pinfunction "RINP_12") (pintype "passive"))
    )
    (net (code "78") (name "Net-(U3-SSCTRL)") (class "Default")
      (node (ref "R4") (pin "1") (pinfunction "1_1") (pintype "passive"))
      (node (ref "R5") (pin "2") (pinfunction "2_2") (pintype "passive"))
      (node (ref "U3") (pin "7") (pinfunction "SSCTRL_7") (pintype "passive"))
    )
    (net (code "79") (name "Net-(U3-~{FAULT})") (class "Default")
      (node (ref "R1") (pin "2") (pinfunction "2_2") (pintype "passive"))
      (node (ref "U3") (pin "1") (pinfunction "~{SD}_1") (pintype "passive"))
      (node (ref "U3") (pin "2") (pinfunction "~{FAULT}_2") (pintype "passive"))
    )
    (net (code "80") (name "unconnected-(DAC-PadA3V3)") (class "Default")
      (node (ref "DAC") (pin "A3V3") (pinfunction "A3V3_A3V3") (pintype "bidirectional"))
    )
    (net (code "81") (name "unconnected-(DAC-PadAGND1)") (class "Default")
      (node (ref "DAC") (pin "AGND1") (pinfunction "AGND1_AGND1") (pintype "bidirectional"))
    )
    (net (code "82") (name "unconnected-(DAC-PadAGND2)") (class "Default")
      (node (ref "DAC") (pin "AGND2") (pinfunction "AGND2_AGND2") (pintype "bidirectional"))
    )
    (net (code "83") (name "unconnected-(DAC-PadDEMP)") (class "Default")
      (node (ref "DAC") (pin "DEMP") (pinfunction "DEMP_DEMP") (pintype "bidirectional"))
    )
    (net (code "84") (name "unconnected-(DAC-PadFLT)") (class "Default")
      (node (ref "DAC") (pin "FLT") (pinfunction "FLT_FLT") (pintype "bidirectional"))
    )
    (net (code "85") (name "unconnected-(DAC-PadFMT)") (class "Default")
      (node (ref "DAC") (pin "FMT") (pinfunction "FMT_FMT") (pintype "bidirectional"))
    )
    (net (code "86") (name "unconnected-(DAC-PadXSMT)") (class "Default")
      (node (ref "DAC") (pin "XSMT") (pinfunction "XSMT_XSMT") (pintype "bidirectional"))
    )
    (net (code "87") (name "unconnected-(IC2-PB4_(MISO{slash}PCINT4)-Pad18)") (class "Default")
      (node (ref "IC2") (pin "18") (pinfunction "PB4_(MISO/PCINT4)_18") (pintype "bidirectional"))
    )
    (net (code "88") (name "unconnected-(IC2-PD2_(PCINT18{slash}INT0)-Pad4)") (class "Default")
      (node (ref "IC2") (pin "4") (pinfunction "PD2_(PCINT18/INT0)_4") (pintype "bidirectional"))
    )
    (net (code "89") (name "unconnected-(IC2-PD3_(PCINT19{slash}OC2B{slash}INT1)-Pad5)") (class "Default")
      (node (ref "IC2") (pin "5") (pinfunction "PD3_(PCINT19/OC2B/INT1)_5") (pintype "bidirectional"))
    )
    (net (code "90") (name "unconnected-(INPUT-NC-Pad7)") (class "Default")
      (node (ref "INPUT") (pin "7") (pinfunction "NC_7") (pintype "no_connect"))
    )
    (net (code "91") (name "unconnected-(LCD-Pad3)") (class "Default")
      (node (ref "LCD") (pin "3") (pinfunction "3_3") (pintype "passive"))
    )
    (net (code "92") (name "unconnected-(LCD-Pad4)") (class "Default")
      (node (ref "LCD") (pin "4") (pinfunction "4_4") (pintype "passive"))
    )
    (net (code "93") (name "unconnected-(LCD-Pad5)") (class "Default")
      (node (ref "LCD") (pin "5") (pinfunction "5_5") (pintype "passive"))
    )
    (net (code "94") (name "unconnected-(LCD-Pad6)") (class "Default")
      (node (ref "LCD") (pin "6") (pinfunction "6_6") (pintype "passive"))
    )
    (net (code "95") (name "unconnected-(LCD-Pad7)") (class "Default")
      (node (ref "LCD") (pin "7") (pinfunction "7_7") (pintype "passive"))
    )
    (net (code "96") (name "unconnected-(LCD-Pad8)") (class "Default")
      (node (ref "LCD") (pin "8") (pinfunction "8_8") (pintype "passive"))
    )
    (net (code "97") (name "unconnected-(LCD-Pad9)") (class "Default")
      (node (ref "LCD") (pin "9") (pinfunction "9_9") (pintype "passive"))
    )
    (net (code "98") (name "unconnected-(LCD-Pad10)") (class "Default")
      (node (ref "LCD") (pin "10") (pinfunction "10_10") (pintype "passive"))
    )
    (net (code "99") (name "unconnected-(LCD-Pad11)") (class "Default")
      (node (ref "LCD") (pin "11") (pinfunction "11_11") (pintype "passive"))
    )
    (net (code "100") (name "unconnected-(LCD-Pad12)") (class "Default")
      (node (ref "LCD") (pin "12") (pinfunction "12_12") (pintype "passive"))
    )
    (net (code "101") (name "unconnected-(LCD-Pad13)") (class "Default")
      (node (ref "LCD") (pin "13") (pinfunction "13_13") (pintype "passive"))
    )
    (net (code "102") (name "unconnected-(LCD-Pad14)") (class "Default")
      (node (ref "LCD") (pin "14") (pinfunction "14_14") (pintype "passive"))
    )
    (net (code "103") (name "unconnected-(LCD-Pad15)") (class "Default")
      (node (ref "LCD") (pin "15") (pinfunction "15_15") (pintype "passive"))
    )
    (net (code "104") (name "unconnected-(LCD-Pad16)") (class "Default")
      (node (ref "LCD") (pin "16") (pinfunction "16_16") (pintype "passive"))
    )
    (net (code "105") (name "unconnected-(LCD-Pad17)") (class "Default")
      (node (ref "LCD") (pin "17") (pinfunction "17_17") (pintype "passive"))
    )
    (net (code "106") (name "unconnected-(LCD-Pad18)") (class "Default")
      (node (ref "LCD") (pin "18") (pinfunction "18_18") (pintype "passive"))
    )
    (net (code "107") (name "unconnected-(LCD-Pad19)") (class "Default")
      (node (ref "LCD") (pin "19") (pinfunction "19_19") (pintype "passive"))
    )
    (net (code "108") (name "unconnected-(LCD-Pad20)") (class "Default")
      (node (ref "LCD") (pin "20") (pinfunction "20_20") (pintype "passive"))
    )
    (net (code "109") (name "unconnected-(LCD-Pad22)") (class "Default")
      (node (ref "LCD") (pin "22") (pinfunction "22_22") (pintype "passive"))
    )
    (net (code "110") (name "unconnected-(LCD-Pad26)") (class "Default")
      (node (ref "LCD") (pin "26") (pinfunction "26_26") (pintype "passive"))
    )
    (net (code "111") (name "unconnected-(LCD-Pad28)") (class "Default")
      (node (ref "LCD") (pin "28") (pinfunction "28_28") (pintype "passive"))
    )
    (net (code "112") (name "unconnected-(LCD-Pad32)") (class "Default")
      (node (ref "LCD") (pin "32") (pinfunction "32_32") (pintype "passive"))
    )
    (net (code "113") (name "unconnected-(LCD-Pad33)") (class "Default")
      (node (ref "LCD") (pin "33") (pinfunction "33_33") (pintype "passive"))
    )
    (net (code "114") (name "unconnected-(LCD-Pad34)") (class "Default")
      (node (ref "LCD") (pin "34") (pinfunction "34_34") (pintype "passive"))
    )
    (net (code "115") (name "unconnected-(LCD-Pad35)") (class "Default")
      (node (ref "LCD") (pin "35") (pinfunction "35_35") (pintype "passive"))
    )
    (net (code "116") (name "unconnected-(LCD-Pad36)") (class "Default")
      (node (ref "LCD") (pin "36") (pinfunction "36_36") (pintype "passive"))
    )
    (net (code "117") (name "unconnected-(LCD-Pad37)") (class "Default")
      (node (ref "LCD") (pin "37") (pinfunction "37_37") (pintype "passive"))
    )
    (net (code "118") (name "unconnected-(LCD-Pad38)") (class "Default")
      (node (ref "LCD") (pin "38") (pinfunction "38_38") (pintype "passive"))
    )
    (net (code "119") (name "unconnected-(OUTPUT-NC-Pad7)") (class "Default")
      (node (ref "OUTPUT") (pin "7") (pinfunction "NC_7") (pintype "no_connect"))
    )
    (net (code "120") (name "unconnected-(PI-Pad1)") (class "Default")
      (node (ref "PI") (pin "1") (pinfunction "1_1") (pintype "passive"))
    )
    (net (code "121") (name "unconnected-(PI-Pad7)") (class "Default")
      (node (ref "PI") (pin "7") (pinfunction "7_7") (pintype "passive"))
    )
    (net (code "122") (name "unconnected-(PI-Pad9)") (class "Default")
      (node (ref "PI") (pin "9") (pinfunction "9_9") (pintype "passive"))
    )
    (net (code "123") (name "unconnected-(PI-Pad13)") (class "Default")
      (node (ref "PI") (pin "13") (pinfunction "13_13") (pintype "passive"))
    )
    (net (code "124") (name "unconnected-(PI-Pad15)") (class "Default")
      (node (ref "PI") (pin "15") (pinfunction "15_15") (pintype "passive"))
    )
    (net (code "125") (name "unconnected-(PI-Pad17)") (class "Default")
      (node (ref "PI") (pin "17") (pinfunction "17_17") (pintype "passive"))
    )
    (net (code "126") (name "unconnected-(PI-Pad20)") (class "Default")
      (node (ref "PI") (pin "20") (pinfunction "20_20") (pintype "passive"))
    )
    (net (code "127") (name "unconnected-(PI-Pad21)") (class "Default")
      (node (ref "PI") (pin "21") (pinfunction "21_21") (pintype "passive"))
    )
    (net (code "128") (name "unconnected-(PI-Pad25)") (class "Default")
      (node (ref "PI") (pin "25") (pinfunction "25_25") (pintype "passive"))
    )
    (net (code "129") (name "unconnected-(PI-Pad27)") (class "Default")
      (node (ref "PI") (pin "27") (pinfunction "27_27") (pintype "passive"))
    )
    (net (code "130") (name "unconnected-(PI-Pad29)") (class "Default")
      (node (ref "PI") (pin "29") (pinfunction "29_29") (pintype "passive"))
    )
    (net (code "131") (name "unconnected-(PI-Pad31)") (class "Default")
      (node (ref "PI") (pin "31") (pinfunction "31_31") (pintype "passive"))
    )
    (net (code "132") (name "unconnected-(PI-Pad32)") (class "Default")
      (node (ref "PI") (pin "32") (pinfunction "32_32") (pintype "passive"))
    )
    (net (code "133") (name "unconnected-(PI-Pad33)") (class "Default")
      (node (ref "PI") (pin "33") (pinfunction "33_33") (pintype "passive"))
    )
    (net (code "134") (name "unconnected-(PI-Pad36)") (class "Default")
      (node (ref "PI") (pin "36") (pinfunction "36_36") (pintype "passive"))
    )
    (net (code "135") (name "unconnected-(PI-Pad38)") (class "Default")
      (node (ref "PI") (pin "38") (pinfunction "38_38") (pintype "passive"))
    )
  )
)
